# main.net
KiCad netlist of a schematic drawn in EAGLE
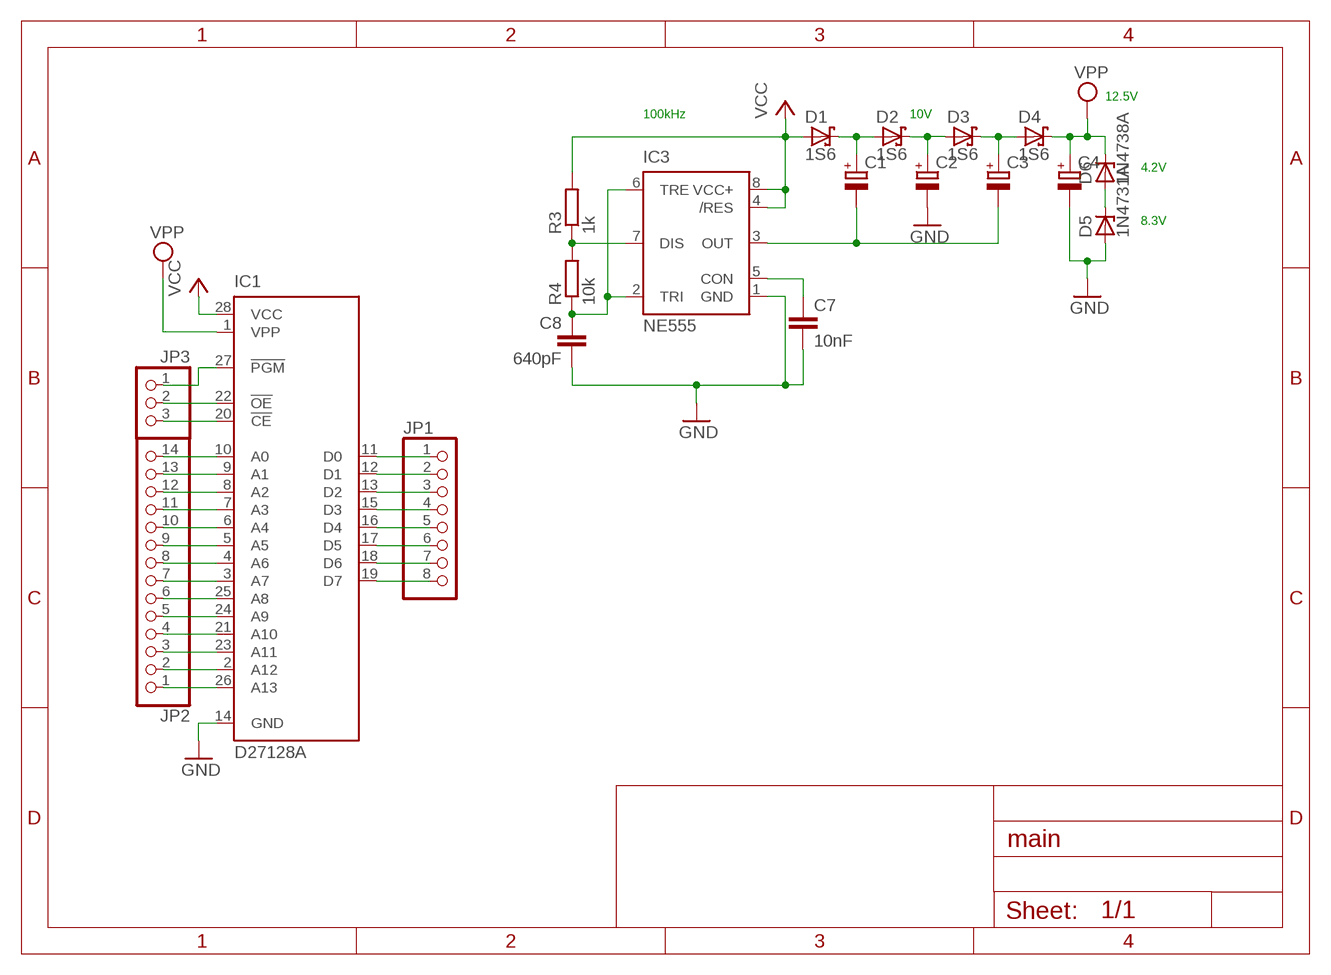
[diagram p0: schematic, sheet 1]

(export (version "E")
  (design (tool "Eeschema 10.0.6"))
  (components
    (comp (ref "C1")
      (value "CPOL-EUB45181A")
      (footprint "eagle-import:B45181A")
      (libsource (lib "eagle-import") (part "CPOL-EUB45181A"))
    )
    (comp (ref "C2")
      (value "CPOL-EUB45181A")
      (footprint "eagle-import:B45181A")
      (libsource (lib "eagle-import") (part "CPOL-EUB45181A"))
    )
    (comp (ref "C3")
      (value "CPOL-EUB45181A")
      (footprint "eagle-import:B45181A")
      (libsource (lib "eagle-import") (part "CPOL-EUB45181A"))
    )
    (comp (ref "C4")
      (value "CPOL-EUB45181A")
      (footprint "eagle-import:B45181A")
      (libsource (lib "eagle-import") (part "CPOL-EUB45181A"))
    )
    (comp (ref "C7")
      (value "10nF")
      (footprint "eagle-import:C025-025X050")
      (libsource (lib "eagle-import") (part "C-EU025-025X050"))
    )
    (comp (ref "C8")
      (value "640pF")
      (footprint "eagle-import:C025-025X050")
      (libsource (lib "eagle-import") (part "C-EU025-025X050"))
    )
    (comp (ref "D1")
      (value "1S6")
      (footprint "eagle-import:DO41-7.6")
      (libsource (lib "eagle-import") (part "1N5817-B"))
    )
    (comp (ref "D2")
      (value "1S6")
      (footprint "eagle-import:DO41-7.6")
      (libsource (lib "eagle-import") (part "1N5817-B"))
    )
    (comp (ref "D3")
      (value "1S6")
      (footprint "eagle-import:DO41-7.6")
      (libsource (lib "eagle-import") (part "1N5817-B"))
    )
    (comp (ref "D4")
      (value "1S6")
      (footprint "eagle-import:DO41-7.6")
      (libsource (lib "eagle-import") (part "1N5817-B"))
    )
    (comp (ref "D5")
      (value "1N4731A")
      (footprint "eagle-import:DO41Z10")
      (libsource (lib "eagle-import") (part "1N4728"))
    )
    (comp (ref "D6")
      (value "1N4738A")
      (footprint "eagle-import:DO41Z10")
      (libsource (lib "eagle-import") (part "1N4728"))
    )
    (comp (ref "IC1")
      (value "D27128A")
      (footprint "eagle-import:DIL28-6")
      (libsource (lib "eagle-import") (part "27128PC"))
    )
    (comp (ref "IC3")
      (value "NE555")
      (footprint "eagle-import:DIL-08")
      (fields (field (name "MF") "Arrow Electronics") (field (name "MPN") "NE555N"))
      (libsource (lib "eagle-import") (part "NE555"))
    )
    (comp (ref "JP1")
      (value "PINHD-1X8")
      (footprint "eagle-import:1X08")
      (libsource (lib "eagle-import") (part "PINHD-1X8"))
    )
    (comp (ref "JP2")
      (value "PINHD-1X14")
      (footprint "eagle-import:1X14")
      (libsource (lib "eagle-import") (part "PINHD-1X14"))
    )
    (comp (ref "JP3")
      (value "PINHD-1X3")
      (footprint "eagle-import:1X03")
      (libsource (lib "eagle-import") (part "PINHD-1X3"))
    )
    (comp (ref "R3")
      (value "1k")
      (footprint "eagle-import:0204_7")
      (libsource (lib "eagle-import") (part "R-EU_0204/7"))
    )
    (comp (ref "R4")
      (value "10k")
      (footprint "eagle-import:0204_7")
      (libsource (lib "eagle-import") (part "R-EU_0204/7"))
    )
  )
  (nets
    (net (code "1") (name "GND") (class "Default")
      (node (ref "C2") (pin "-") (pinfunction "-_-") (pintype "passive"))
      (node (ref "C4") (pin "-") (pinfunction "-_-") (pintype "passive"))
      (node (ref "C7") (pin "2") (pinfunction "2_2") (pintype "passive"))
      (node (ref "C8") (pin "2") (pinfunction "2_2") (pintype "passive"))
      (node (ref "D5") (pin "A") (pinfunction "A_A") (pintype "passive"))
      (node (ref "IC1") (pin "14") (pinfunction "GND_14") (pintype "power_in"))
      (node (ref "IC3") (pin "1") (pinfunction "GND_1") (pintype "power_in"))
    )
    (net (code "2") (name "Net-(C1-Pad+)") (class "Default")
      (node (ref "C1") (pin "+") (pinfunction "+_+") (pintype "passive"))
      (node (ref "D1") (pin "C") (pinfunction "C_C") (pintype "passive"))
      (node (ref "D2") (pin "A") (pinfunction "A_A") (pintype "passive"))
    )
    (net (code "3") (name "Net-(C2-Pad+)") (class "Default")
      (node (ref "C2") (pin "+") (pinfunction "+_+") (pintype "passive"))
      (node (ref "D2") (pin "C") (pinfunction "C_C") (pintype "passive"))
      (node (ref "D3") (pin "A") (pinfunction "A_A") (pintype "passive"))
    )
    (net (code "4") (name "Net-(C3-Pad+)") (class "Default")
      (node (ref "C3") (pin "+") (pinfunction "+_+") (pintype "passive"))
      (node (ref "D3") (pin "C") (pinfunction "C_C") (pintype "passive"))
      (node (ref "D4") (pin "A") (pinfunction "A_A") (pintype "passive"))
    )
    (net (code "5") (name "Net-(D5-PadC)") (class "Default")
      (node (ref "D5") (pin "C") (pinfunction "C_C") (pintype "passive"))
      (node (ref "D6") (pin "A") (pinfunction "A_A") (pintype "passive"))
    )
    (net (code "6") (name "Net-(IC1-A0)") (class "Default")
      (node (ref "IC1") (pin "10") (pinfunction "A0_10") (pintype "input"))
      (node (ref "JP2") (pin "14") (pinfunction "14_14") (pintype "passive"))
    )
    (net (code "7") (name "Net-(IC1-A1)") (class "Default")
      (node (ref "IC1") (pin "9") (pinfunction "A1_9") (pintype "input"))
      (node (ref "JP2") (pin "13") (pinfunction "13_13") (pintype "passive"))
    )
    (net (code "8") (name "Net-(IC1-A2)") (class "Default")
      (node (ref "IC1") (pin "8") (pinfunction "A2_8") (pintype "input"))
      (node (ref "JP2") (pin "12") (pinfunction "12_12") (pintype "passive"))
    )
    (net (code "9") (name "Net-(IC1-A3)") (class "Default")
      (node (ref "IC1") (pin "7") (pinfunction "A3_7") (pintype "input"))
      (node (ref "JP2") (pin "11") (pinfunction "11_11") (pintype "passive"))
    )
    (net (code "10") (name "Net-(IC1-A4)") (class "Default")
      (node (ref "IC1") (pin "6") (pinfunction "A4_6") (pintype "input"))
      (node (ref "JP2") (pin "10") (pinfunction "10_10") (pintype "passive"))
    )
    (net (code "11") (name "Net-(IC1-A5)") (class "Default")
      (node (ref "IC1") (pin "5") (pinfunction "A5_5") (pintype "input"))
      (node (ref "JP2") (pin "9") (pinfunction "9_9") (pintype "passive"))
    )
    (net (code "12") (name "Net-(IC1-A6)") (class "Default")
      (node (ref "IC1") (pin "4") (pinfunction "A6_4") (pintype "input"))
      (node (ref "JP2") (pin "8") (pinfunction "8_8") (pintype "passive"))
    )
    (net (code "13") (name "Net-(IC1-A7)") (class "Default")
      (node (ref "IC1") (pin "3") (pinfunction "A7_3") (pintype "input"))
      (node (ref "JP2") (pin "7") (pinfunction "7_7") (pintype "passive"))
    )
    (net (code "14") (name "Net-(IC1-A8)") (class "Default")
      (node (ref "IC1") (pin "25") (pinfunction "A8_25") (pintype "input"))
      (node (ref "JP2") (pin "6") (pinfunction "6_6") (pintype "passive"))
    )
    (net (code "15") (name "Net-(IC1-A9)") (class "Default")
      (node (ref "IC1") (pin "24") (pinfunction "A9_24") (pintype "input"))
      (node (ref "JP2") (pin "5") (pinfunction "5_5") (pintype "passive"))
    )
    (net (code "16") (name "Net-(IC1-A10)") (class "Default")
      (node (ref "IC1") (pin "21") (pinfunction "A10_21") (pintype "input"))
      (node (ref "JP2") (pin "4") (pinfunction "4_4") (pintype "passive"))
    )
    (net (code "17") (name "Net-(IC1-A11)") (class "Default")
      (node (ref "IC1") (pin "23") (pinfunction "A11_23") (pintype "input"))
      (node (ref "JP2") (pin "3") (pinfunction "3_3") (pintype "passive"))
    )
    (net (code "18") (name "Net-(IC1-A12)") (class "Default")
      (node (ref "IC1") (pin "2") (pinfunction "A12_2") (pintype "input"))
      (node (ref "JP2") (pin "2") (pinfunction "2_2") (pintype "passive"))
    )
    (net (code "19") (name "Net-(IC1-A13)") (class "Default")
      (node (ref "IC1") (pin "26") (pinfunction "A13_26") (pintype "input"))
      (node (ref "JP2") (pin "1") (pinfunction "1_1") (pintype "passive"))
    )
    (net (code "20") (name "Net-(IC1-D0)") (class "Default")
      (node (ref "IC1") (pin "11") (pinfunction "D0_11") (pintype "tri_state"))
      (node (ref "JP1") (pin "1") (pinfunction "1_1") (pintype "passive"))
    )
    (net (code "21") (name "Net-(IC1-D1)") (class "Default")
      (node (ref "IC1") (pin "12") (pinfunction "D1_12") (pintype "tri_state"))
      (node (ref "JP1") (pin "2") (pinfunction "2_2") (pintype "passive"))
    )
    (net (code "22") (name "Net-(IC1-D2)") (class "Default")
      (node (ref "IC1") (pin "13") (pinfunction "D2_13") (pintype "tri_state"))
      (node (ref "JP1") (pin "3") (pinfunction "3_3") (pintype "passive"))
    )
    (net (code "23") (name "Net-(IC1-D3)") (class "Default")
      (node (ref "IC1") (pin "15") (pinfunction "D3_15") (pintype "tri_state"))
      (node (ref "JP1") (pin "4") (pinfunction "4_4") (pintype "passive"))
    )
    (net (code "24") (name "Net-(IC1-D4)") (class "Default")
      (node (ref "IC1") (pin "16") (pinfunction "D4_16") (pintype "tri_state"))
      (node (ref "JP1") (pin "5") (pinfunction "5_5") (pintype "passive"))
    )
    (net (code "25") (name "Net-(IC1-D5)") (class "Default")
      (node (ref "IC1") (pin "17") (pinfunction "D5_17") (pintype "tri_state"))
      (node (ref "JP1") (pin "6") (pinfunction "6_6") (pintype "passive"))
    )
    (net (code "26") (name "Net-(IC1-D6)") (class "Default")
      (node (ref "IC1") (pin "18") (pinfunction "D6_18") (pintype "tri_state"))
      (node (ref "JP1") (pin "7") (pinfunction "7_7") (pintype "passive"))
    )
    (net (code "27") (name "Net-(IC1-D7)") (class "Default")
      (node (ref "IC1") (pin "19") (pinfunction "D7_19") (pintype "tri_state"))
      (node (ref "JP1") (pin "8") (pinfunction "8_8") (pintype "passive"))
    )
    (net (code "28") (name "Net-(IC1-~{CE})") (class "Default")
      (node (ref "IC1") (pin "20") (pinfunction "~{CE}_20") (pintype "input"))
      (node (ref "JP3") (pin "3") (pinfunction "3_3") (pintype "passive"))
    )
    (net (code "29") (name "Net-(IC1-~{OE})") (class "Default")
      (node (ref "IC1") (pin "22") (pinfunction "~{OE}_22") (pintype "input"))
      (node (ref "JP3") (pin "2") (pinfunction "2_2") (pintype "passive"))
    )
    (net (code "30") (name "Net-(IC1-~{PGM})") (class "Default")
      (node (ref "IC1") (pin "27") (pinfunction "~{PGM}_27") (pintype "passive"))
      (node (ref "JP3") (pin "1") (pinfunction "1_1") (pintype "passive"))
    )
    (net (code "31") (name "Net-(IC3-CON)") (class "Default")
      (node (ref "C7") (pin "1") (pinfunction "1_1") (pintype "passive"))
      (node (ref "IC3") (pin "5") (pinfunction "CON_5") (pintype "input"))
    )
    (net (code "32") (name "Net-(IC3-DIS)") (class "Default")
      (node (ref "IC3") (pin "7") (pinfunction "DIS_7") (pintype "input"))
      (node (ref "R3") (pin "1") (pinfunction "1_1") (pintype "passive"))
      (node (ref "R4") (pin "2") (pinfunction "2_2") (pintype "passive"))
    )
    (net (code "33") (name "Net-(IC3-OUT)") (class "Default")
      (node (ref "C1") (pin "-") (pinfunction "-_-") (pintype "passive"))
      (node (ref "C3") (pin "-") (pinfunction "-_-") (pintype "passive"))
      (node (ref "IC3") (pin "3") (pinfunction "OUT_3") (pintype "output"))
    )
    (net (code "34") (name "Net-(IC3-TRE)") (class "Default")
      (node (ref "C8") (pin "1") (pinfunction "1_1") (pintype "passive"))
      (node (ref "IC3") (pin "2") (pinfunction "TRI_2") (pintype "input"))
      (node (ref "IC3") (pin "6") (pinfunction "TRE_6") (pintype "input"))
      (node (ref "R4") (pin "1") (pinfunction "1_1") (pintype "passive"))
    )
    (net (code "35") (name "VCC") (class "Default")
      (node (ref "D1") (pin "A") (pinfunction "A_A") (pintype "passive"))
      (node (ref "IC1") (pin "28") (pinfunction "VCC_28") (pintype "power_in"))
      (node (ref "IC3") (pin "4") (pinfunction "/RES_4") (pintype "input"))
      (node (ref "IC3") (pin "8") (pinfunction "VCC+_8") (pintype "power_in"))
      (node (ref "R3") (pin "2") (pinfunction "2_2") (pintype "passive"))
    )
    (net (code "36") (name "VPP") (class "Default")
      (node (ref "C4") (pin "+") (pinfunction "+_+") (pintype "passive"))
      (node (ref "D4") (pin "C") (pinfunction "C_C") (pintype "passive"))
      (node (ref "D6") (pin "C") (pinfunction "C_C") (pintype "passive"))
      (node (ref "IC1") (pin "1") (pinfunction "VPP_1") (pintype "input"))
    )
  )
)
